# Transimpedance_Amplifier.net
KiCad netlist of a schematic drawn in Altium Designer
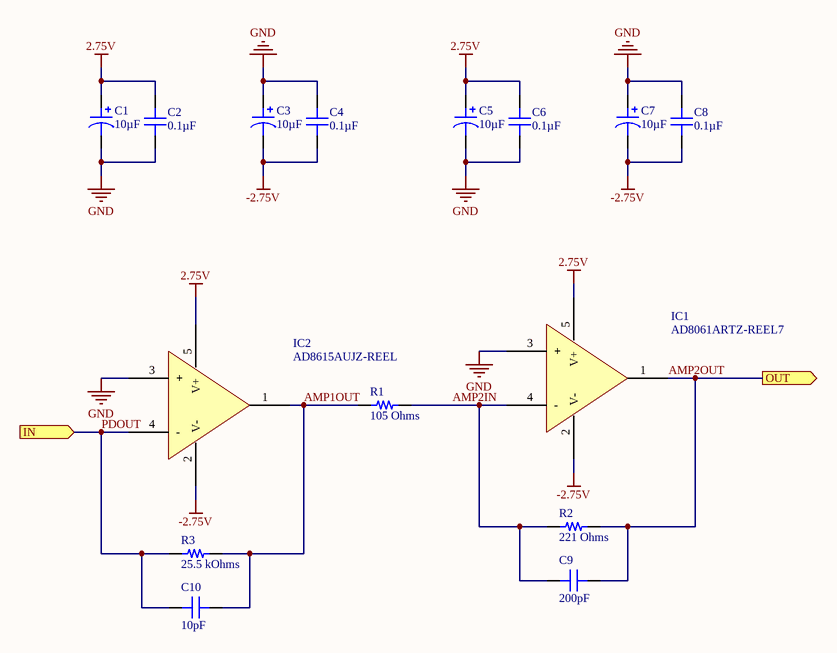
[diagram p0: Transimpedance Amplifier.SchDoc]

(export (version "E")
  (design (tool "Eeschema 10.0.6"))
  (components
    (comp (ref "C1")
      (value "10µF")
      (footprint "CAP POL 1206_3216")
      (description "CAP TANT POLY 10UF 6.3V 1206")
      (fields (field (name "PART NUMBER") "T55A106M6R3C0200") (field (name "MANUFACTURER") "Vishay Sprague"))
      (libsource (lib "Celestial Altium Library - altium_library") (part "Polarised Capacitor"))
    )
    (comp (ref "C2")
      (value "0.1µF")
      (footprint "CAP 0603_1608")
      (description "CAP CER 0.1UF 25V Y5V 0603")
      (fields (field (name "PART NUMBER") "CC0603MRY5V8BB104") (field (name "MANUFACTURER") "Yageo"))
      (libsource (lib "Celestial Altium Library - altium_library") (part "Capacitor"))
    )
    (comp (ref "C3")
      (value "10µF")
      (footprint "CAP POL 1206_3216")
      (description "CAP TANT POLY 10UF 6.3V 1206")
      (fields (field (name "PART NUMBER") "T55A106M6R3C0200") (field (name "MANUFACTURER") "Vishay Sprague"))
      (libsource (lib "Celestial Altium Library - altium_library") (part "Polarised Capacitor"))
    )
    (comp (ref "C4")
      (value "0.1µF")
      (footprint "CAP 0603_1608")
      (description "CAP CER 0.1UF 25V Y5V 0603")
      (fields (field (name "PART NUMBER") "CC0603MRY5V8BB104") (field (name "MANUFACTURER") "Yageo"))
      (libsource (lib "Celestial Altium Library - altium_library") (part "Capacitor"))
    )
    (comp (ref "C5")
      (value "10µF")
      (footprint "CAP POL 1206_3216")
      (description "CAP TANT POLY 10UF 6.3V 1206")
      (fields (field (name "PART NUMBER") "T55A106M6R3C0200") (field (name "MANUFACTURER") "Vishay Sprague"))
      (libsource (lib "Celestial Altium Library - altium_library") (part "Polarised Capacitor"))
    )
    (comp (ref "C6")
      (value "0.1µF")
      (footprint "CAP 0603_1608")
      (description "CAP CER 0.1UF 25V Y5V 0603")
      (fields (field (name "PART NUMBER") "CC0603MRY5V8BB104") (field (name "MANUFACTURER") "Yageo"))
      (libsource (lib "Celestial Altium Library - altium_library") (part "Capacitor"))
    )
    (comp (ref "C7")
      (value "10µF")
      (footprint "CAP POL 1206_3216")
      (description "CAP TANT POLY 10UF 6.3V 1206")
      (fields (field (name "PART NUMBER") "T55A106M6R3C0200") (field (name "MANUFACTURER") "Vishay Sprague"))
      (libsource (lib "Celestial Altium Library - altium_library") (part "Polarised Capacitor"))
    )
    (comp (ref "C8")
      (value "0.1µF")
      (footprint "CAP 0603_1608")
      (description "CAP CER 0.1UF 25V Y5V 0603")
      (fields (field (name "PART NUMBER") "CC0603MRY5V8BB104") (field (name "MANUFACTURER") "Yageo"))
      (libsource (lib "Celestial Altium Library - altium_library") (part "Capacitor"))
    )
    (comp (ref "C9")
      (value "200pF")
      (footprint "CAP 0603_1608")
      (description "CAP CER 200PF 50V X7R 0603")
      (fields (field (name "PART NUMBER") "CC0603KRX7R9BB201") (field (name "MANUFACTURER") "Yageo"))
      (libsource (lib "Celestial Altium Library - altium_library") (part "Capacitor"))
    )
    (comp (ref "C10")
      (value "10pF")
      (footprint "CAP 0603_1608")
      (description "CAP CER 10PF 50V C0G/NP0 0603")
      (fields (field (name "PART NUMBER") "06035A100JAT2A") (field (name "MANUFACTURER") "AVX Corporation"))
      (libsource (lib "Celestial Altium Library - altium_library") (part "Capacitor"))
    )
    (comp (ref "IC1")
      (value "AD8061ARTZ-REEL7")
      (footprint "ANALOG SOT-23-5 RJ-5")
      (description "IC OPAMP VFB 1 CIRCUIT SOT23-5")
      (fields (field (name "MANUFACTURER") "Analog Devices Inc."))
      (libsource (lib "Celestial Altium Library - altium_library") (part "ANALOG DEV AD8061ARTZ"))
    )
    (comp (ref "IC2")
      (value "AD8615AUJZ-REEL")
      (footprint "ANALOG TSOT-23-5 UJ-5")
      (description "IC OPAMP GP 1 CIRCUIT TSOT23-5")
      (fields (field (name "MANUFACTURER") "Analog Devices Inc."))
      (libsource (lib "Celestial Altium Library - altium_library") (part "ANALOG DEV AD8615AUJZ"))
    )
    (comp (ref "R1")
      (value "105 Ohms")
      (footprint "RES 0603_1608")
      (description "RES SMD 105 OHM 1% 1/10W 0603")
      (fields
        (field (name "PART NUMBER") "ERJ-3EKF1050V")
        (field (name "MANUFACTURER") "Panasonic Electronic Components")
      )
      (libsource (lib "Celestial Altium Library - altium_library") (part "Resistor"))
    )
    (comp (ref "R2")
      (value "221 Ohms")
      (footprint "RES 0603_1608")
      (description "RES SMD 221 OHM 1% 1/10W 0603")
      (fields
        (field (name "PART NUMBER") "ERJ-3EKF2210V")
        (field (name "MANUFACTURER") "Panasonic Electronic Components")
      )
      (libsource (lib "Celestial Altium Library - altium_library") (part "Resistor"))
    )
    (comp (ref "R3")
      (value "25.5 kOhms")
      (footprint "RES 0603_1608")
      (description "RES SMD 25.5K OHM 1% 1/10W 0603")
      (fields
        (field (name "PART NUMBER") "ERJ-3EKF2552V")
        (field (name "MANUFACTURER") "Panasonic Electronic Components")
      )
      (libsource (lib "Celestial Altium Library - altium_library") (part "Resistor"))
    )
  )
  (nets
    (net (code "1") (name "-2.75V") (class "Default")
      (node (ref "C3") (pin "2") (pinfunction "2_2") (pintype "passive"))
      (node (ref "C4") (pin "1") (pinfunction "1_1") (pintype "passive"))
      (node (ref "C7") (pin "2") (pinfunction "2_2") (pintype "passive"))
      (node (ref "C8") (pin "1") (pinfunction "1_1") (pintype "passive"))
      (node (ref "IC1") (pin "2") (pinfunction "V-_2") (pintype "passive"))
      (node (ref "IC2") (pin "2") (pinfunction "V-_2") (pintype "passive"))
    )
    (net (code "2") (name "/AMP1OUT") (class "Default")
      (node (ref "C10") (pin "1") (pinfunction "1_1") (pintype "passive"))
      (node (ref "IC2") (pin "1") (pinfunction "OUT_1") (pintype "passive"))
      (node (ref "R1") (pin "1") (pinfunction "1_1") (pintype "passive"))
      (node (ref "R3") (pin "2") (pinfunction "2_2") (pintype "passive"))
    )
    (net (code "3") (name "/AMP2IN") (class "Default")
      (node (ref "C9") (pin "1") (pinfunction "1_1") (pintype "passive"))
      (node (ref "IC1") (pin "4") (pinfunction "-_4") (pintype "passive"))
      (node (ref "R1") (pin "2") (pinfunction "2_2") (pintype "passive"))
      (node (ref "R2") (pin "1") (pinfunction "1_1") (pintype "passive"))
    )
    (net (code "4") (name "/AMP2OUT") (class "Default")
      (node (ref "C9") (pin "2") (pinfunction "2_2") (pintype "passive"))
      (node (ref "IC1") (pin "1") (pinfunction "OUT_1") (pintype "passive"))
      (node (ref "R2") (pin "2") (pinfunction "2_2") (pintype "passive"))
    )
    (net (code "5") (name "/PDOUT") (class "Default")
      (node (ref "C10") (pin "2") (pinfunction "2_2") (pintype "passive"))
      (node (ref "IC2") (pin "4") (pinfunction "-_4") (pintype "passive"))
      (node (ref "R3") (pin "1") (pinfunction "1_1") (pintype "passive"))
    )
    (net (code "6") (name "2.75V") (class "Default")
      (node (ref "C1") (pin "1") (pinfunction "1_1") (pintype "passive"))
      (node (ref "C2") (pin "2") (pinfunction "2_2") (pintype "passive"))
      (node (ref "C5") (pin "1") (pinfunction "1_1") (pintype "passive"))
      (node (ref "C6") (pin "2") (pinfunction "2_2") (pintype "passive"))
      (node (ref "IC1") (pin "5") (pinfunction "V+_5") (pintype "passive"))
      (node (ref "IC2") (pin "5") (pinfunction "V+_5") (pintype "passive"))
    )
    (net (code "7") (name "GND") (class "Default")
      (node (ref "C1") (pin "2") (pinfunction "2_2") (pintype "passive"))
      (node (ref "C2") (pin "1") (pinfunction "1_1") (pintype "passive"))
      (node (ref "C3") (pin "1") (pinfunction "1_1") (pintype "passive"))
      (node (ref "C4") (pin "2") (pinfunction "2_2") (pintype "passive"))
      (node (ref "C5") (pin "2") (pinfunction "2_2") (pintype "passive"))
      (node (ref "C6") (pin "1") (pinfunction "1_1") (pintype "passive"))
      (node (ref "C7") (pin "1") (pinfunction "1_1") (pintype "passive"))
      (node (ref "C8") (pin "2") (pinfunction "2_2") (pintype "passive"))
      (node (ref "IC1") (pin "3") (pinfunction "+_3") (pintype "passive"))
      (node (ref "IC2") (pin "3") (pinfunction "+_3") (pintype "passive"))
    )
  )
)
